# 3ch_mix_1_6.net
KiCad netlist of a schematic drawn in EAGLE
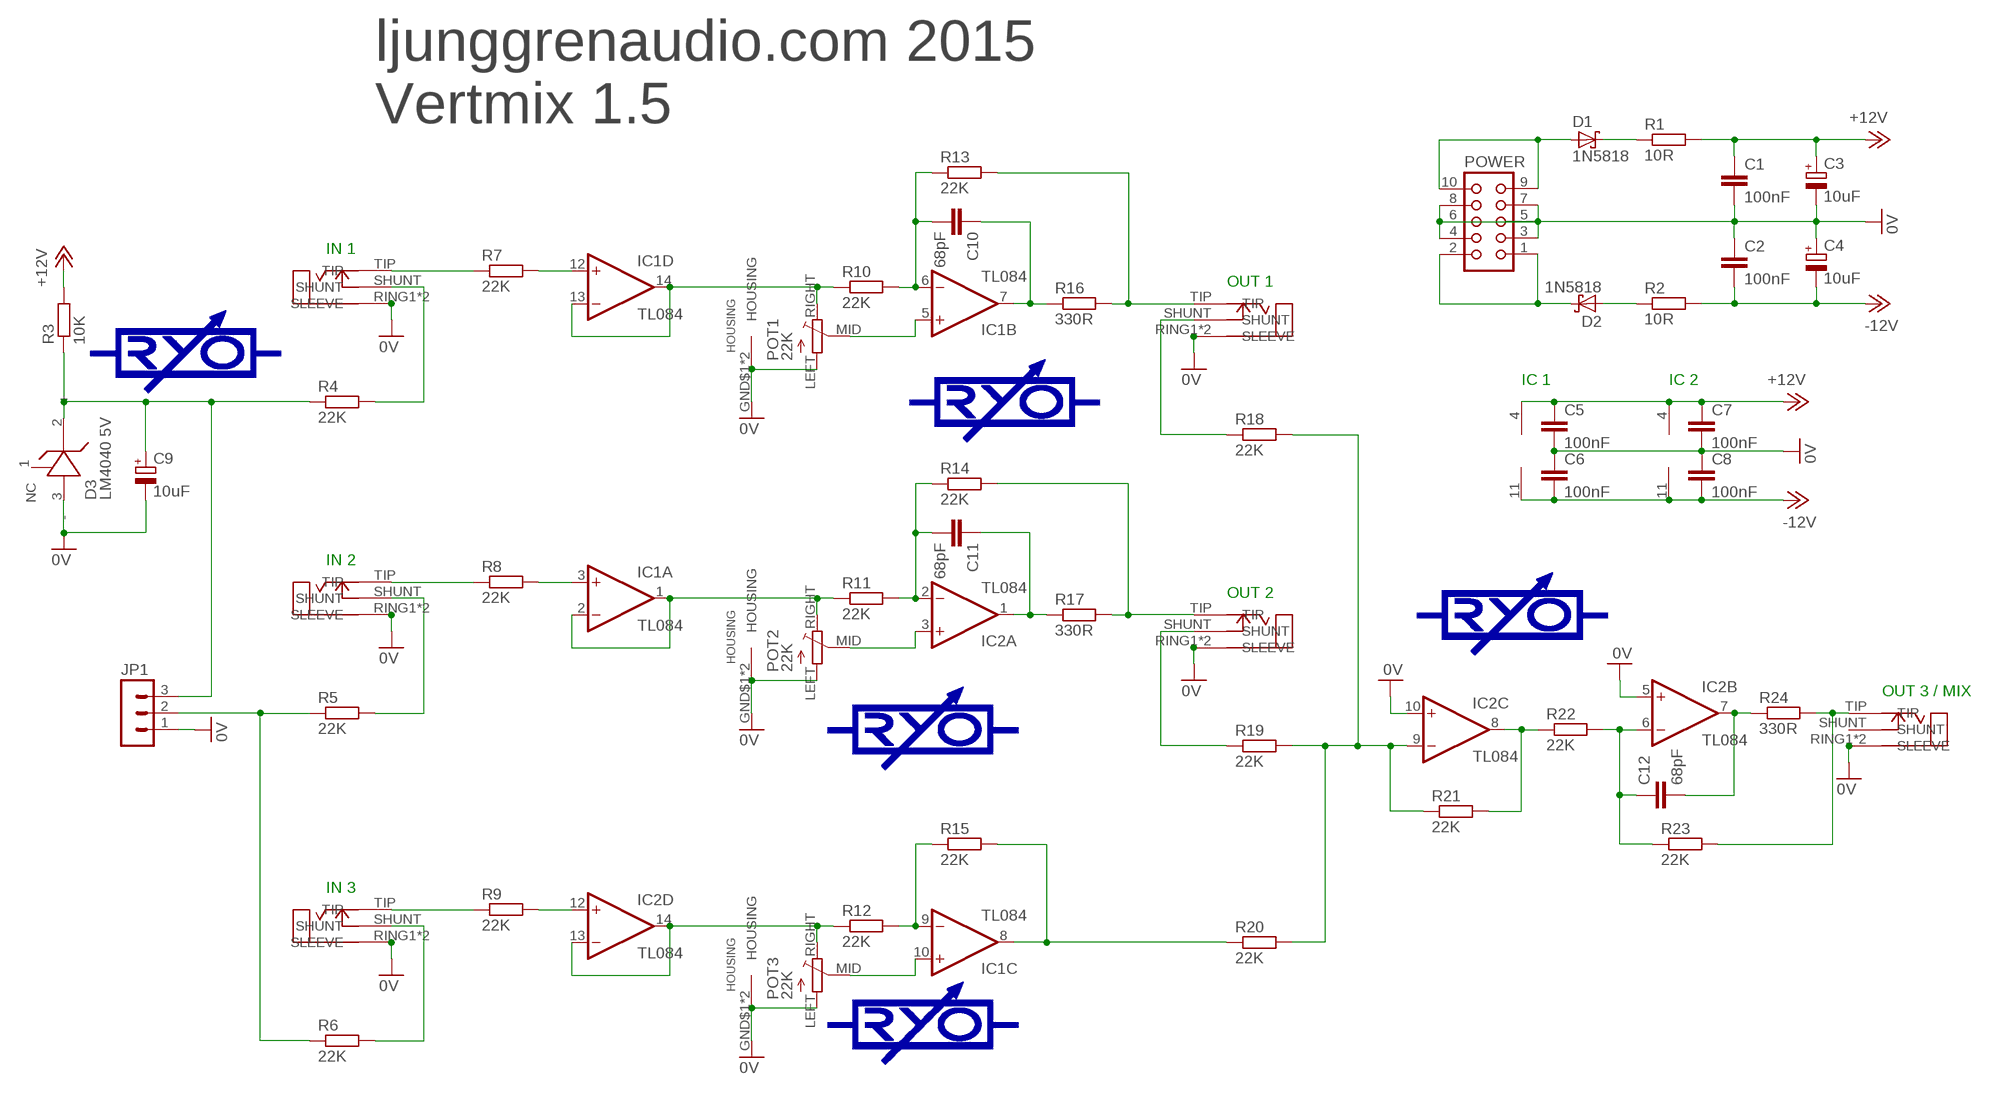
[diagram p0: schematic, sheet 1]

(export (version "E")
  (design (tool "Eeschema 10.0.6"))
  (components
    (comp (ref "C1")
      (value "100nF")
      (footprint "eagle-import:C0805K")
      (libsource (lib "eagle-import") (part "C-EUC0805K"))
    )
    (comp (ref "C2")
      (value "100nF")
      (footprint "eagle-import:C0805K")
      (libsource (lib "eagle-import") (part "C-EUC0805K"))
    )
    (comp (ref "C3")
      (value "10uF")
      (footprint "eagle-import:E2-5")
      (libsource (lib "eagle-import") (part "CPOL-EUE2-5"))
    )
    (comp (ref "C4")
      (value "10uF")
      (footprint "eagle-import:E2-5")
      (libsource (lib "eagle-import") (part "CPOL-EUE2-5"))
    )
    (comp (ref "C5")
      (value "100nF")
      (footprint "eagle-import:C0805K")
      (libsource (lib "eagle-import") (part "C-EUC0805K"))
    )
    (comp (ref "C6")
      (value "100nF")
      (footprint "eagle-import:C0805K")
      (libsource (lib "eagle-import") (part "C-EUC0805K"))
    )
    (comp (ref "C7")
      (value "100nF")
      (footprint "eagle-import:C0805K")
      (libsource (lib "eagle-import") (part "C-EUC0805K"))
    )
    (comp (ref "C8")
      (value "100nF")
      (footprint "eagle-import:C0805K")
      (libsource (lib "eagle-import") (part "C-EUC0805K"))
    )
    (comp (ref "C9")
      (value "10uF")
      (footprint "eagle-import:E2-5")
      (libsource (lib "eagle-import") (part "CPOL-EUE2-5"))
    )
    (comp (ref "C10")
      (value "68pF")
      (footprint "eagle-import:C0805K")
      (libsource (lib "eagle-import") (part "C-EUC0805K"))
    )
    (comp (ref "C11")
      (value "68pF")
      (footprint "eagle-import:C0805K")
      (libsource (lib "eagle-import") (part "C-EUC0805K"))
    )
    (comp (ref "C12")
      (value "68pF")
      (footprint "eagle-import:C0805K")
      (libsource (lib "eagle-import") (part "C-EUC0805K"))
    )
    (comp (ref "D1")
      (value "1N5818")
      (footprint "eagle-import:DO41-7")
      (libsource (lib "eagle-import") (part "SB130DO-204AL"))
    )
    (comp (ref "D2")
      (value "1N5818")
      (footprint "eagle-import:DO41-7")
      (libsource (lib "eagle-import") (part "SB130DO-204AL"))
    )
    (comp (ref "D3")
      (value "LM4040 5V")
      (footprint "eagle-import:TO92-LINE")
      (libsource (lib "eagle-import") (part "LM4040"))
    )
    (comp (ref "IC1")
      (value "TL084")
      (footprint "eagle-import:DIL14")
      (libsource (lib "eagle-import") (part "TL074P"))
    )
    (comp (ref "IC2")
      (value "TL084")
      (footprint "eagle-import:DIL14")
      (libsource (lib "eagle-import") (part "TL074P"))
    )
    (comp (ref "IN1")
      (value "ERTHENVAR_3.5MM_JACKHOLES")
      (footprint "eagle-import:ERTHENVAR")
      (libsource (lib "eagle-import") (part "ERTHENVAR_3.5MM_JACKHOLES"))
    )
    (comp (ref "IN2")
      (value "ERTHENVAR_3.5MM_JACKHOLES")
      (footprint "eagle-import:ERTHENVAR")
      (libsource (lib "eagle-import") (part "ERTHENVAR_3.5MM_JACKHOLES"))
    )
    (comp (ref "IN3")
      (value "ERTHENVAR_3.5MM_JACKHOLES")
      (footprint "eagle-import:ERTHENVAR")
      (libsource (lib "eagle-import") (part "ERTHENVAR_3.5MM_JACKHOLES"))
    )
    (comp (ref "JP1")
      (value "MA03-1")
      (footprint "eagle-import:MA03-1")
      (libsource (lib "eagle-import") (part "MA03-1"))
    )
    (comp (ref "OUT1")
      (value "ERTHENVAR_3.5MM_JACKHOLES")
      (footprint "eagle-import:ERTHENVAR")
      (libsource (lib "eagle-import") (part "ERTHENVAR_3.5MM_JACKHOLES"))
    )
    (comp (ref "OUT2")
      (value "ERTHENVAR_3.5MM_JACKHOLES")
      (footprint "eagle-import:ERTHENVAR")
      (libsource (lib "eagle-import") (part "ERTHENVAR_3.5MM_JACKHOLES"))
    )
    (comp (ref "OUT3")
      (value "ERTHENVAR_3.5MM_JACKHOLES")
      (footprint "eagle-import:ERTHENVAR")
      (libsource (lib "eagle-import") (part "ERTHENVAR_3.5MM_JACKHOLES"))
    )
    (comp (ref "POT1")
      (value "22K")
      (footprint "eagle-import:POT-ALPHA9")
      (libsource (lib "eagle-import") (part "POT-ALPHA9"))
    )
    (comp (ref "POT2")
      (value "22K")
      (footprint "eagle-import:POT-ALPHA9")
      (libsource (lib "eagle-import") (part "POT-ALPHA9"))
    )
    (comp (ref "POT3")
      (value "22K")
      (footprint "eagle-import:POT-ALPHA9")
      (libsource (lib "eagle-import") (part "POT-ALPHA9"))
    )
    (comp (ref "POWER")
      (value "CON10L")
      (footprint "eagle-import:CON10L")
      (libsource (lib "eagle-import") (part "CON10L"))
    )
    (comp (ref "R1")
      (value "10R")
      (footprint "eagle-import:C0805K")
      (libsource (lib "eagle-import") (part "R-EU_R0805K"))
    )
    (comp (ref "R2")
      (value "10R")
      (footprint "eagle-import:C0805K")
      (libsource (lib "eagle-import") (part "R-EU_R0805K"))
    )
    (comp (ref "R3")
      (value "10K")
      (footprint "eagle-import:C0805K")
      (libsource (lib "eagle-import") (part "R-EU_R0805K"))
    )
    (comp (ref "R4")
      (value "22K")
      (footprint "eagle-import:C0805K")
      (libsource (lib "eagle-import") (part "R-EU_R0805K"))
    )
    (comp (ref "R5")
      (value "22K")
      (footprint "eagle-import:C0805K")
      (libsource (lib "eagle-import") (part "R-EU_R0805K"))
    )
    (comp (ref "R6")
      (value "22K")
      (footprint "eagle-import:C0805K")
      (libsource (lib "eagle-import") (part "R-EU_R0805K"))
    )
    (comp (ref "R7")
      (value "22K")
      (footprint "eagle-import:C0805K")
      (libsource (lib "eagle-import") (part "R-EU_R0805K"))
    )
    (comp (ref "R8")
      (value "22K")
      (footprint "eagle-import:C0805K")
      (libsource (lib "eagle-import") (part "R-EU_R0805K"))
    )
    (comp (ref "R9")
      (value "22K")
      (footprint "eagle-import:C0805K")
      (libsource (lib "eagle-import") (part "R-EU_R0805K"))
    )
    (comp (ref "R10")
      (value "22K")
      (footprint "eagle-import:C0805K")
      (libsource (lib "eagle-import") (part "R-EU_R0805K"))
    )
    (comp (ref "R11")
      (value "22K")
      (footprint "eagle-import:C0805K")
      (libsource (lib "eagle-import") (part "R-EU_R0805K"))
    )
    (comp (ref "R12")
      (value "22K")
      (footprint "eagle-import:C0805K")
      (libsource (lib "eagle-import") (part "R-EU_R0805K"))
    )
    (comp (ref "R13")
      (value "22K")
      (footprint "eagle-import:C0805K")
      (libsource (lib "eagle-import") (part "R-EU_R0805K"))
    )
    (comp (ref "R14")
      (value "22K")
      (footprint "eagle-import:C0805K")
      (libsource (lib "eagle-import") (part "R-EU_R0805K"))
    )
    (comp (ref "R15")
      (value "22K")
      (footprint "eagle-import:C0805K")
      (libsource (lib "eagle-import") (part "R-EU_R0805K"))
    )
    (comp (ref "R16")
      (value "330R")
      (footprint "eagle-import:C0805K")
      (libsource (lib "eagle-import") (part "R-EU_R0805K"))
    )
    (comp (ref "R17")
      (value "330R")
      (footprint "eagle-import:C0805K")
      (libsource (lib "eagle-import") (part "R-EU_R0805K"))
    )
    (comp (ref "R18")
      (value "22K")
      (footprint "eagle-import:C0805K")
      (libsource (lib "eagle-import") (part "R-EU_R0805K"))
    )
    (comp (ref "R19")
      (value "22K")
      (footprint "eagle-import:C0805K")
      (libsource (lib "eagle-import") (part "R-EU_R0805K"))
    )
    (comp (ref "R20")
      (value "22K")
      (footprint "eagle-import:C0805K")
      (libsource (lib "eagle-import") (part "R-EU_R0805K"))
    )
    (comp (ref "R21")
      (value "22K")
      (footprint "eagle-import:C0805K")
      (libsource (lib "eagle-import") (part "R-EU_R0805K"))
    )
    (comp (ref "R22")
      (value "22K")
      (footprint "eagle-import:C0805K")
      (libsource (lib "eagle-import") (part "R-EU_R0805K"))
    )
    (comp (ref "R23")
      (value "22K")
      (footprint "eagle-import:C0805K")
      (libsource (lib "eagle-import") (part "R-EU_R0805K"))
    )
    (comp (ref "R24")
      (value "330R")
      (footprint "eagle-import:C0805K")
      (libsource (lib "eagle-import") (part "R-EU_R0805K"))
    )
  )
  (nets
    (net (code "1") (name "+12V") (class "Default")
      (node (ref "C1") (pin "1") (pinfunction "1_1") (pintype "passive"))
      (node (ref "C3") (pin "+") (pinfunction "+_+") (pintype "passive"))
      (node (ref "C5") (pin "1") (pinfunction "1_1") (pintype "passive"))
      (node (ref "C7") (pin "1") (pinfunction "1_1") (pintype "passive"))
      (node (ref "IC1") (pin "4") (pinfunction "V+_4") (pintype "power_in"))
      (node (ref "IC2") (pin "4") (pinfunction "V+_4") (pintype "power_in"))
      (node (ref "R1") (pin "2") (pinfunction "2_2") (pintype "passive"))
      (node (ref "R3") (pin "2") (pinfunction "2_2") (pintype "passive"))
    )
    (net (code "2") (name "-12V") (class "Default")
      (node (ref "C2") (pin "2") (pinfunction "2_2") (pintype "passive"))
      (node (ref "C4") (pin "-") (pinfunction "-_-") (pintype "passive"))
      (node (ref "C6") (pin "2") (pinfunction "2_2") (pintype "passive"))
      (node (ref "C8") (pin "2") (pinfunction "2_2") (pintype "passive"))
      (node (ref "IC1") (pin "11") (pinfunction "V-_11") (pintype "power_in"))
      (node (ref "IC2") (pin "11") (pinfunction "V-_11") (pintype "power_in"))
      (node (ref "R2") (pin "2") (pinfunction "2_2") (pintype "passive"))
    )
    (net (code "3") (name "0V") (class "Default")
      (node (ref "C1") (pin "2") (pinfunction "2_2") (pintype "passive"))
      (node (ref "C2") (pin "1") (pinfunction "1_1") (pintype "passive"))
      (node (ref "C3") (pin "-") (pinfunction "-_-") (pintype "passive"))
      (node (ref "C4") (pin "+") (pinfunction "+_+") (pintype "passive"))
      (node (ref "C5") (pin "2") (pinfunction "2_2") (pintype "passive"))
      (node (ref "C6") (pin "1") (pinfunction "1_1") (pintype "passive"))
      (node (ref "C7") (pin "2") (pinfunction "2_2") (pintype "passive"))
      (node (ref "C8") (pin "1") (pinfunction "1_1") (pintype "passive"))
      (node (ref "C9") (pin "-") (pinfunction "-_-") (pintype "passive"))
      (node (ref "D3") (pin "3") (pinfunction "-_3") (pintype "bidirectional"))
      (node (ref "IC2") (pin "10") (pinfunction "+IN_10") (pintype "input"))
      (node (ref "IC2") (pin "5") (pinfunction "+IN_5") (pintype "input"))
      (node (ref "IN1") (pin "RING1") (pinfunction "SLEEVE_RING1") (pintype "bidirectional"))
      (node (ref "IN1") (pin "RING2") (pinfunction "SLEEVE_RING2") (pintype "bidirectional"))
      (node (ref "IN2") (pin "RING1") (pinfunction "SLEEVE_RING1") (pintype "bidirectional"))
      (node (ref "IN2") (pin "RING2") (pinfunction "SLEEVE_RING2") (pintype "bidirectional"))
      (node (ref "IN3") (pin "RING1") (pinfunction "SLEEVE_RING1") (pintype "bidirectional"))
      (node (ref "IN3") (pin "RING2") (pinfunction "SLEEVE_RING2") (pintype "bidirectional"))
      (node (ref "JP1") (pin "1") (pinfunction "1_1") (pintype "passive"))
      (node (ref "OUT1") (pin "RING1") (pinfunction "SLEEVE_RING1") (pintype "bidirectional"))
      (node (ref "OUT1") (pin "RING2") (pinfunction "SLEEVE_RING2") (pintype "bidirectional"))
      (node (ref "OUT2") (pin "RING1") (pinfunction "SLEEVE_RING1") (pintype "bidirectional"))
      (node (ref "OUT2") (pin "RING2") (pinfunction "SLEEVE_RING2") (pintype "bidirectional"))
      (node (ref "OUT3") (pin "RING1") (pinfunction "SLEEVE_RING1") (pintype "bidirectional"))
      (node (ref "OUT3") (pin "RING2") (pinfunction "SLEEVE_RING2") (pintype "bidirectional"))
      (node (ref "POT1") (pin "GND$1") (pinfunction "HOUSING_GND$1") (pintype "bidirectional"))
      (node (ref "POT1") (pin "GND$2") (pinfunction "HOUSING_GND$2") (pintype "bidirectional"))
      (node (ref "POT1") (pin "LEFT") (pinfunction "LEFT_LEFT") (pintype "passive"))
      (node (ref "POT2") (pin "GND$1") (pinfunction "HOUSING_GND$1") (pintype "bidirectional"))
      (node (ref "POT2") (pin "GND$2") (pinfunction "HOUSING_GND$2") (pintype "bidirectional"))
      (node (ref "POT2") (pin "LEFT") (pinfunction "LEFT_LEFT") (pintype "passive"))
      (node (ref "POT3") (pin "GND$1") (pinfunction "HOUSING_GND$1") (pintype "bidirectional"))
      (node (ref "POT3") (pin "GND$2") (pinfunction "HOUSING_GND$2") (pintype "bidirectional"))
      (node (ref "POT3") (pin "LEFT") (pinfunction "LEFT_LEFT") (pintype "passive"))
      (node (ref "POWER") (pin "3") (pinfunction "3_3") (pintype "passive"))
      (node (ref "POWER") (pin "4") (pinfunction "4_4") (pintype "passive"))
      (node (ref "POWER") (pin "5") (pinfunction "5_5") (pintype "passive"))
      (node (ref "POWER") (pin "6") (pinfunction "6_6") (pintype "passive"))
      (node (ref "POWER") (pin "7") (pinfunction "7_7") (pintype "passive"))
      (node (ref "POWER") (pin "8") (pinfunction "8_8") (pintype "passive"))
    )
    (net (code "4") (name "Net-(D1-PadA)") (class "Default")
      (node (ref "D1") (pin "A") (pinfunction "A_A") (pintype "passive"))
      (node (ref "POWER") (pin "10") (pinfunction "10_10") (pintype "passive"))
      (node (ref "POWER") (pin "9") (pinfunction "9_9") (pintype "passive"))
    )
    (net (code "5") (name "Net-(D1-PadC)") (class "Default")
      (node (ref "D1") (pin "C") (pinfunction "C_C") (pintype "passive"))
      (node (ref "R1") (pin "1") (pinfunction "1_1") (pintype "passive"))
    )
    (net (code "6") (name "Net-(D2-PadA)") (class "Default")
      (node (ref "D2") (pin "A") (pinfunction "A_A") (pintype "passive"))
      (node (ref "R2") (pin "1") (pinfunction "1_1") (pintype "passive"))
    )
    (net (code "7") (name "Net-(D2-PadC)") (class "Default")
      (node (ref "D2") (pin "C") (pinfunction "C_C") (pintype "passive"))
      (node (ref "POWER") (pin "1") (pinfunction "1_1") (pintype "passive"))
      (node (ref "POWER") (pin "2") (pinfunction "2_2") (pintype "passive"))
    )
    (net (code "8") (name "Net-(D3-+)") (class "Default")
      (node (ref "C9") (pin "+") (pinfunction "+_+") (pintype "passive"))
      (node (ref "D3") (pin "2") (pinfunction "+_2") (pintype "bidirectional"))
      (node (ref "JP1") (pin "3") (pinfunction "3_3") (pintype "passive"))
      (node (ref "R3") (pin "1") (pinfunction "1_1") (pintype "passive"))
      (node (ref "R4") (pin "1") (pinfunction "1_1") (pintype "passive"))
    )
    (net (code "9") (name "Net-(IC1A-+IN)") (class "Default")
      (node (ref "IC1") (pin "3") (pinfunction "+IN_3") (pintype "input"))
      (node (ref "R8") (pin "2") (pinfunction "2_2") (pintype "passive"))
    )
    (net (code "10") (name "Net-(IC1A--IN)") (class "Default")
      (node (ref "IC1") (pin "1") (pinfunction "OUT_1") (pintype "output"))
      (node (ref "IC1") (pin "2") (pinfunction "-IN_2") (pintype "input"))
      (node (ref "POT2") (pin "RIGHT") (pinfunction "RIGHT_RIGHT") (pintype "passive"))
      (node (ref "R11") (pin "1") (pinfunction "1_1") (pintype "passive"))
    )
    (net (code "11") (name "Net-(IC1B-+IN)") (class "Default")
      (node (ref "IC1") (pin "5") (pinfunction "+IN_5") (pintype "input"))
      (node (ref "POT1") (pin "MID") (pinfunction "MID_MID") (pintype "passive"))
    )
    (net (code "12") (name "Net-(IC1B--IN)") (class "Default")
      (node (ref "C10") (pin "2") (pinfunction "2_2") (pintype "passive"))
      (node (ref "IC1") (pin "6") (pinfunction "-IN_6") (pintype "input"))
      (node (ref "R10") (pin "2") (pinfunction "2_2") (pintype "passive"))
      (node (ref "R13") (pin "1") (pinfunction "1_1") (pintype "passive"))
    )
    (net (code "13") (name "Net-(IC1B-OUT)") (class "Default")
      (node (ref "C10") (pin "1") (pinfunction "1_1") (pintype "passive"))
      (node (ref "IC1") (pin "7") (pinfunction "OUT_7") (pintype "output"))
      (node (ref "R16") (pin "1") (pinfunction "1_1") (pintype "passive"))
    )
    (net (code "14") (name "Net-(IC1C-+IN)") (class "Default")
      (node (ref "IC1") (pin "10") (pinfunction "+IN_10") (pintype "input"))
      (node (ref "POT3") (pin "MID") (pinfunction "MID_MID") (pintype "passive"))
    )
    (net (code "15") (name "Net-(IC1C--IN)") (class "Default")
      (node (ref "IC1") (pin "9") (pinfunction "-IN_9") (pintype "input"))
      (node (ref "R12") (pin "2") (pinfunction "2_2") (pintype "passive"))
      (node (ref "R15") (pin "1") (pinfunction "1_1") (pintype "passive"))
    )
    (net (code "16") (name "Net-(IC1C-OUT)") (class "Default")
      (node (ref "IC1") (pin "8") (pinfunction "OUT_8") (pintype "output"))
      (node (ref "R15") (pin "2") (pinfunction "2_2") (pintype "passive"))
      (node (ref "R20") (pin "1") (pinfunction "1_1") (pintype "passive"))
    )
    (net (code "17") (name "Net-(IC1D-+IN)") (class "Default")
      (node (ref "IC1") (pin "12") (pinfunction "+IN_12") (pintype "input"))
      (node (ref "R7") (pin "2") (pinfunction "2_2") (pintype "passive"))
    )
    (net (code "18") (name "Net-(IC1D--IN)") (class "Default")
      (node (ref "IC1") (pin "13") (pinfunction "-IN_13") (pintype "input"))
      (node (ref "IC1") (pin "14") (pinfunction "OUT_14") (pintype "output"))
      (node (ref "POT1") (pin "RIGHT") (pinfunction "RIGHT_RIGHT") (pintype "passive"))
      (node (ref "R10") (pin "1") (pinfunction "1_1") (pintype "passive"))
    )
    (net (code "19") (name "Net-(IC2A-+IN)") (class "Default")
      (node (ref "IC2") (pin "3") (pinfunction "+IN_3") (pintype "input"))
      (node (ref "POT2") (pin "MID") (pinfunction "MID_MID") (pintype "passive"))
    )
    (net (code "20") (name "Net-(IC2A--IN)") (class "Default")
      (node (ref "C11") (pin "2") (pinfunction "2_2") (pintype "passive"))
      (node (ref "IC2") (pin "2") (pinfunction "-IN_2") (pintype "input"))
      (node (ref "R11") (pin "2") (pinfunction "2_2") (pintype "passive"))
      (node (ref "R14") (pin "1") (pinfunction "1_1") (pintype "passive"))
    )
    (net (code "21") (name "Net-(IC2A-OUT)") (class "Default")
      (node (ref "C11") (pin "1") (pinfunction "1_1") (pintype "passive"))
      (node (ref "IC2") (pin "1") (pinfunction "OUT_1") (pintype "output"))
      (node (ref "R17") (pin "1") (pinfunction "1_1") (pintype "passive"))
    )
    (net (code "22") (name "Net-(IC2B--IN)") (class "Default")
      (node (ref "C12") (pin "1") (pinfunction "1_1") (pintype "passive"))
      (node (ref "IC2") (pin "6") (pinfunction "-IN_6") (pintype "input"))
      (node (ref "R22") (pin "2") (pinfunction "2_2") (pintype "passive"))
      (node (ref "R23") (pin "1") (pinfunction "1_1") (pintype "passive"))
    )
    (net (code "23") (name "Net-(IC2B-OUT)") (class "Default")
      (node (ref "C12") (pin "2") (pinfunction "2_2") (pintype "passive"))
      (node (ref "IC2") (pin "7") (pinfunction "OUT_7") (pintype "output"))
      (node (ref "R24") (pin "1") (pinfunction "1_1") (pintype "passive"))
    )
    (net (code "24") (name "Net-(IC2C--IN)") (class "Default")
      (node (ref "IC2") (pin "9") (pinfunction "-IN_9") (pintype "input"))
      (node (ref "R18") (pin "2") (pinfunction "2_2") (pintype "passive"))
      (node (ref "R19") (pin "2") (pinfunction "2_2") (pintype "passive"))
      (node (ref "R20") (pin "2") (pinfunction "2_2") (pintype "passive"))
      (node (ref "R21") (pin "1") (pinfunction "1_1") (pintype "passive"))
    )
    (net (code "25") (name "Net-(IC2C-OUT)") (class "Default")
      (node (ref "IC2") (pin "8") (pinfunction "OUT_8") (pintype "output"))
      (node (ref "R21") (pin "2") (pinfunction "2_2") (pintype "passive"))
      (node (ref "R22") (pin "1") (pinfunction "1_1") (pintype "passive"))
    )
    (net (code "26") (name "Net-(IC2D-+IN)") (class "Default")
      (node (ref "IC2") (pin "12") (pinfunction "+IN_12") (pintype "input"))
      (node (ref "R9") (pin "2") (pinfunction "2_2") (pintype "passive"))
    )
    (net (code "27") (name "Net-(IC2D--IN)") (class "Default")
      (node (ref "IC2") (pin "13") (pinfunction "-IN_13") (pintype "input"))
      (node (ref "IC2") (pin "14") (pinfunction "OUT_14") (pintype "output"))
      (node (ref "POT3") (pin "RIGHT") (pinfunction "RIGHT_RIGHT") (pintype "passive"))
      (node (ref "R12") (pin "1") (pinfunction "1_1") (pintype "passive"))
    )
    (net (code "28") (name "Net-(IN1-PadSHUNT)") (class "Default")
      (node (ref "IN1") (pin "SHUNT") (pinfunction "SHUNT_SHUNT") (pintype "bidirectional"))
      (node (ref "R4") (pin "2") (pinfunction "2_2") (pintype "passive"))
    )
    (net (code "29") (name "Net-(IN1-PadTIP)") (class "Default")
      (node (ref "IN1") (pin "TIP") (pinfunction "TIP_TIP") (pintype "bidirectional"))
      (node (ref "R7") (pin "1") (pinfunction "1_1") (pintype "passive"))
    )
    (net (code "30") (name "Net-(IN2-PadSHUNT)") (class "Default")
      (node (ref "IN2") (pin "SHUNT") (pinfunction "SHUNT_SHUNT") (pintype "bidirectional"))
      (node (ref "R5") (pin "2") (pinfunction "2_2") (pintype "passive"))
    )
    (net (code "31") (name "Net-(IN2-PadTIP)") (class "Default")
      (node (ref "IN2") (pin "TIP") (pinfunction "TIP_TIP") (pintype "bidirectional"))
      (node (ref "R8") (pin "1") (pinfunction "1_1") (pintype "passive"))
    )
    (net (code "32") (name "Net-(IN3-PadSHUNT)") (class "Default")
      (node (ref "IN3") (pin "SHUNT") (pinfunction "SHUNT_SHUNT") (pintype "bidirectional"))
      (node (ref "R6") (pin "2") (pinfunction "2_2") (pintype "passive"))
    )
    (net (code "33") (name "Net-(IN3-PadTIP)") (class "Default")
      (node (ref "IN3") (pin "TIP") (pinfunction "TIP_TIP") (pintype "bidirectional"))
      (node (ref "R9") (pin "1") (pinfunction "1_1") (pintype "passive"))
    )
    (net (code "34") (name "Net-(JP1-Pad2)") (class "Default")
      (node (ref "JP1") (pin "2") (pinfunction "2_2") (pintype "passive"))
      (node (ref "R5") (pin "1") (pinfunction "1_1") (pintype "passive"))
      (node (ref "R6") (pin "1") (pinfunction "1_1") (pintype "passive"))
    )
    (net (code "35") (name "Net-(OUT1-PadSHUNT)") (class "Default")
      (node (ref "OUT1") (pin "SHUNT") (pinfunction "SHUNT_SHUNT") (pintype "bidirectional"))
      (node (ref "R18") (pin "1") (pinfunction "1_1") (pintype "passive"))
    )
    (net (code "36") (name "Net-(OUT1-PadTIP)") (class "Default")
      (node (ref "OUT1") (pin "TIP") (pinfunction "TIP_TIP") (pintype "bidirectional"))
      (node (ref "R13") (pin "2") (pinfunction "2_2") (pintype "passive"))
      (node (ref "R16") (pin "2") (pinfunction "2_2") (pintype "passive"))
    )
    (net (code "37") (name "Net-(OUT2-PadSHUNT)") (class "Default")
      (node (ref "OUT2") (pin "SHUNT") (pinfunction "SHUNT_SHUNT") (pintype "bidirectional"))
      (node (ref "R19") (pin "1") (pinfunction "1_1") (pintype "passive"))
    )
    (net (code "38") (name "Net-(OUT2-PadTIP)") (class "Default")
      (node (ref "OUT2") (pin "TIP") (pinfunction "TIP_TIP") (pintype "bidirectional"))
      (node (ref "R14") (pin "2") (pinfunction "2_2") (pintype "passive"))
      (node (ref "R17") (pin "2") (pinfunction "2_2") (pintype "passive"))
    )
    (net (code "39") (name "Net-(OUT3-PadTIP)") (class "Default")
      (node (ref "OUT3") (pin "TIP") (pinfunction "TIP_TIP") (pintype "bidirectional"))
      (node (ref "R23") (pin "2") (pinfunction "2_2") (pintype "passive"))
      (node (ref "R24") (pin "2") (pinfunction "2_2") (pintype "passive"))
    )
    (net (code "40") (name "unconnected-(D3-NC-Pad1)") (class "Default")
      (node (ref "D3") (pin "1") (pinfunction "NC_1") (pintype "no_connect"))
    )
    (net (code "41") (name "unconnected-(OUT3-PadSHUNT)") (class "Default")
      (node (ref "OUT3") (pin "SHUNT") (pinfunction "SHUNT_SHUNT") (pintype "bidirectional"))
    )
  )
)
